# PCA9685Shield.net
KiCad netlist of a schematic drawn in EAGLE
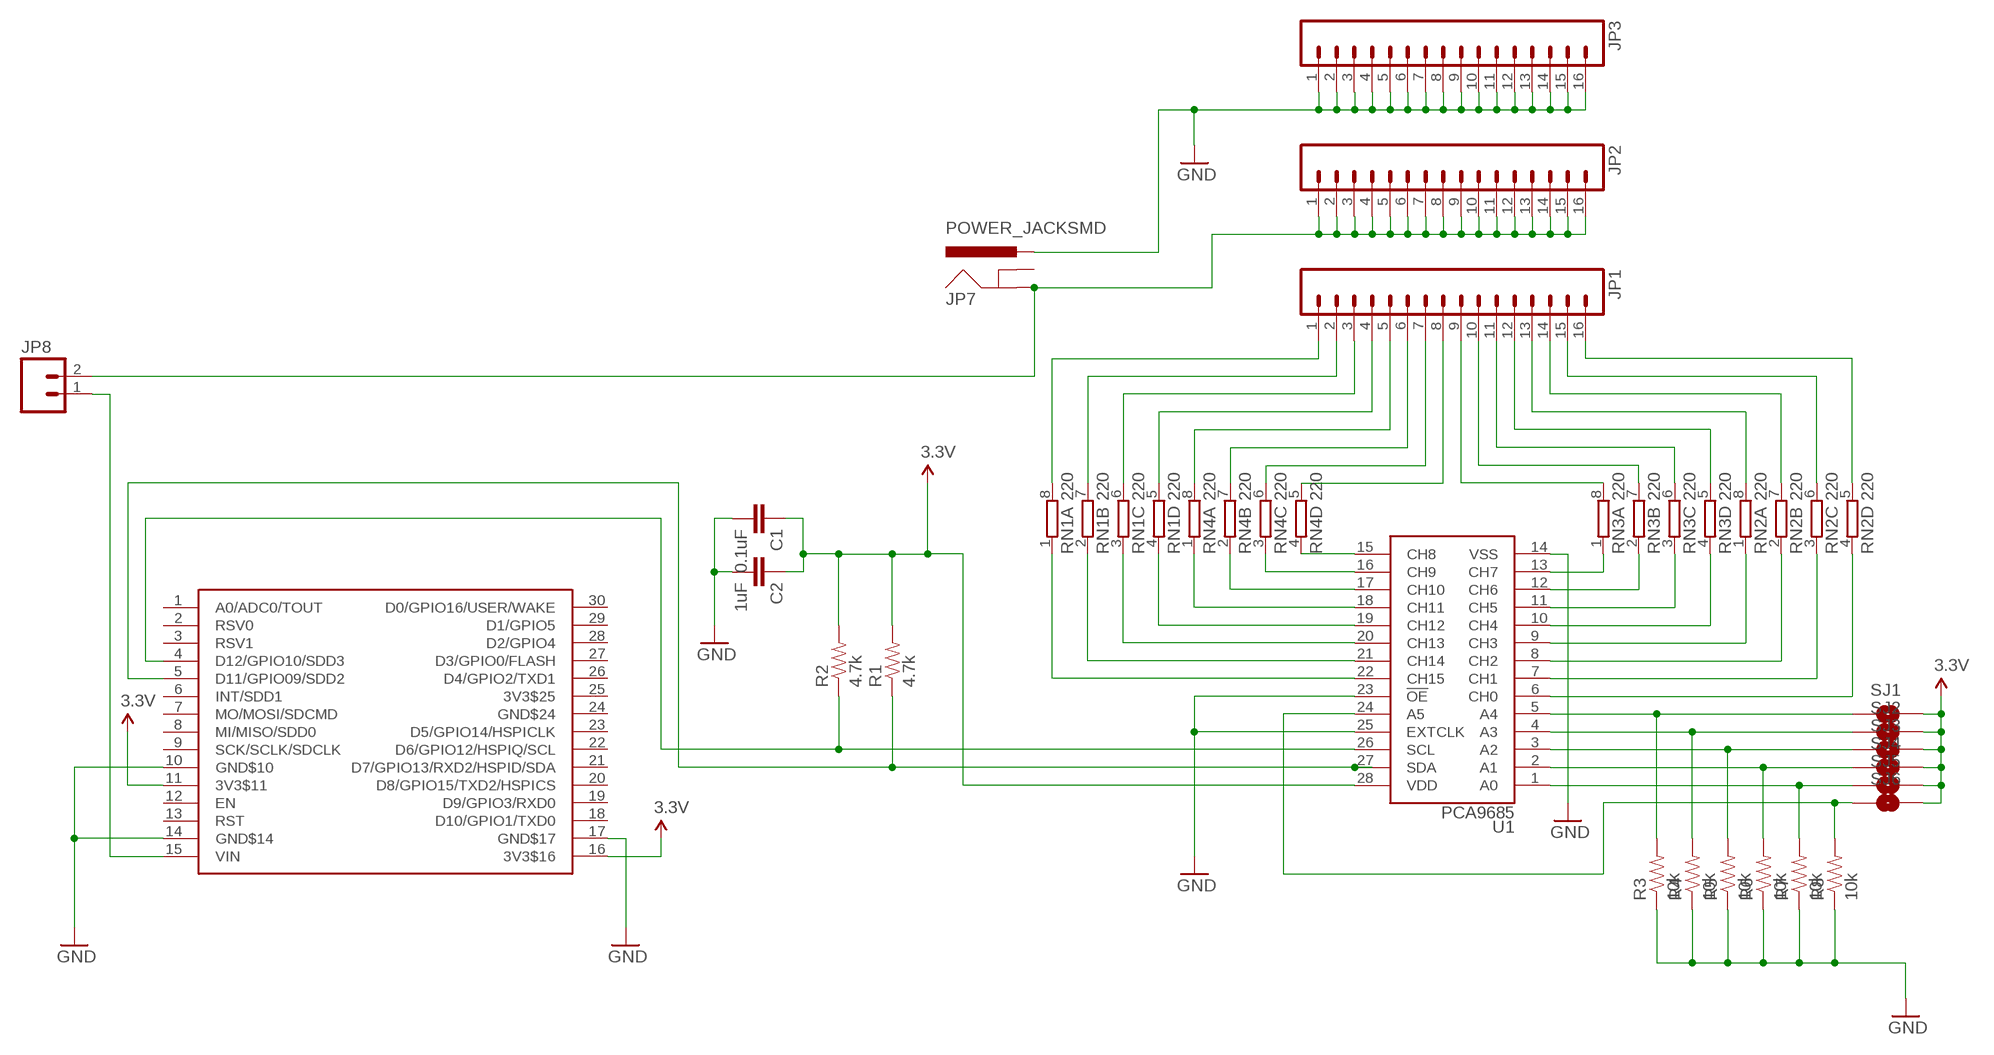
[diagram p0: schematic, sheet 1]

(export (version "E")
  (design (tool "Eeschema 10.0.6"))
  (components
    (comp (ref "C1")
      (value "0.1uF")
      (footprint "eagle-import:0402-CAP")
      (libsource (lib "eagle-import") (part "CAP0402-CAP"))
    )
    (comp (ref "C2")
      (value "1uF")
      (footprint "eagle-import:0402-CAP")
      (libsource (lib "eagle-import") (part "CAP0402-CAP"))
    )
    (comp (ref "JP1")
      (value "M161X16_NO_SILK")
      (footprint "eagle-import:1X16_NO_SILK")
      (libsource (lib "eagle-import") (part "M161X16_NO_SILK"))
    )
    (comp (ref "JP2")
      (value "M161X16_NO_SILK")
      (footprint "eagle-import:1X16_NO_SILK")
      (libsource (lib "eagle-import") (part "M161X16_NO_SILK"))
    )
    (comp (ref "JP3")
      (value "M161X16_NO_SILK")
      (footprint "eagle-import:1X16_NO_SILK")
      (libsource (lib "eagle-import") (part "M161X16_NO_SILK"))
    )
    (comp (ref "JP7")
      (value "POWER_JACKSMD")
      (footprint "eagle-import:POWER_JACK_SMD")
      (libsource (lib "eagle-import") (part "POWER_JACKSMD"))
    )
    (comp (ref "JP8")
      (value "M021X02_NO_SILK")
      (footprint "eagle-import:1X02_NO_SILK")
      (libsource (lib "eagle-import") (part "M021X02_NO_SILK"))
    )
    (comp (ref "R1")
      (value "4.7k")
      (footprint "eagle-import:0402-RES")
      (libsource (lib "eagle-import") (part "RESISTOR0402-RES"))
    )
    (comp (ref "R2")
      (value "4.7k")
      (footprint "eagle-import:0402-RES")
      (libsource (lib "eagle-import") (part "RESISTOR0402-RES"))
    )
    (comp (ref "R3")
      (value "10k")
      (footprint "eagle-import:0402-RES")
      (libsource (lib "eagle-import") (part "RESISTOR0402-RES"))
    )
    (comp (ref "R4")
      (value "10k")
      (footprint "eagle-import:0402-RES")
      (libsource (lib "eagle-import") (part "RESISTOR0402-RES"))
    )
    (comp (ref "R5")
      (value "10k")
      (footprint "eagle-import:0402-RES")
      (libsource (lib "eagle-import") (part "RESISTOR0402-RES"))
    )
    (comp (ref "R6")
      (value "10k")
      (footprint "eagle-import:0402-RES")
      (libsource (lib "eagle-import") (part "RESISTOR0402-RES"))
    )
    (comp (ref "R7")
      (value "10k")
      (footprint "eagle-import:0402-RES")
      (libsource (lib "eagle-import") (part "RESISTOR0402-RES"))
    )
    (comp (ref "R8")
      (value "10k")
      (footprint "eagle-import:0402-RES")
      (libsource (lib "eagle-import") (part "RESISTOR0402-RES"))
    )
    (comp (ref "RN1")
      (value "220")
      (footprint "eagle-import:EXBS8V")
      (libsource (lib "eagle-import") (part "4R-NEXBS8V"))
    )
    (comp (ref "RN2")
      (value "220")
      (footprint "eagle-import:EXBS8V")
      (libsource (lib "eagle-import") (part "4R-NEXBS8V"))
    )
    (comp (ref "RN3")
      (value "220")
      (footprint "eagle-import:EXBS8V")
      (libsource (lib "eagle-import") (part "4R-NEXBS8V"))
    )
    (comp (ref "RN4")
      (value "220")
      (footprint "eagle-import:EXBS8V")
      (libsource (lib "eagle-import") (part "4R-NEXBS8V"))
    )
    (comp (ref "SJ1")
      (value "SOLDERJUMPERNO")
      (footprint "eagle-import:SJ_2S-NO")
      (libsource (lib "eagle-import") (part "SOLDERJUMPERNO"))
    )
    (comp (ref "SJ2")
      (value "SOLDERJUMPERNO")
      (footprint "eagle-import:SJ_2S-NO")
      (libsource (lib "eagle-import") (part "SOLDERJUMPERNO"))
    )
    (comp (ref "SJ3")
      (value "SOLDERJUMPERNO")
      (footprint "eagle-import:SJ_2S-NO")
      (libsource (lib "eagle-import") (part "SOLDERJUMPERNO"))
    )
    (comp (ref "SJ4")
      (value "SOLDERJUMPERNO")
      (footprint "eagle-import:SJ_2S-NO")
      (libsource (lib "eagle-import") (part "SOLDERJUMPERNO"))
    )
    (comp (ref "SJ5")
      (value "SOLDERJUMPERNO")
      (footprint "eagle-import:SJ_2S-NO")
      (libsource (lib "eagle-import") (part "SOLDERJUMPERNO"))
    )
    (comp (ref "SJ6")
      (value "SOLDERJUMPERNO")
      (footprint "eagle-import:SJ_2S-NO")
      (libsource (lib "eagle-import") (part "SOLDERJUMPERNO"))
    )
    (comp (ref "U$1")
      (value "NERDSHIELD")
      (footprint "eagle-import:NERDUINO_STACK")
      (libsource (lib "eagle-import") (part "NERDSHIELD"))
    )
    (comp (ref "U1")
      (value "PCA9685")
      (footprint "eagle-import:TSSOP-28_4MM")
      (libsource (lib "eagle-import") (part "PCA9685"))
    )
  )
  (nets
    (net (code "1") (name "3.3V") (class "Default")
      (node (ref "C1") (pin "1") (pinfunction "1_1") (pintype "passive"))
      (node (ref "C2") (pin "1") (pinfunction "1_1") (pintype "passive"))
      (node (ref "R1") (pin "2") (pinfunction "2_2") (pintype "passive"))
      (node (ref "R2") (pin "2") (pinfunction "2_2") (pintype "passive"))
      (node (ref "SJ1") (pin "2") (pinfunction "2_2") (pintype "passive"))
      (node (ref "SJ2") (pin "2") (pinfunction "2_2") (pintype "passive"))
      (node (ref "SJ3") (pin "2") (pinfunction "2_2") (pintype "passive"))
      (node (ref "SJ4") (pin "2") (pinfunction "2_2") (pintype "passive"))
      (node (ref "SJ5") (pin "2") (pinfunction "2_2") (pintype "passive"))
      (node (ref "SJ6") (pin "2") (pinfunction "2_2") (pintype "passive"))
      (node (ref "U$1") (pin "11") (pinfunction "3V3$11_11") (pintype "bidirectional"))
      (node (ref "U$1") (pin "16") (pinfunction "3V3$16_16") (pintype "bidirectional"))
      (node (ref "U1") (pin "28") (pinfunction "VDD_28") (pintype "bidirectional"))
    )
    (net (code "2") (name "GND") (class "Default")
      (node (ref "C1") (pin "2") (pinfunction "2_2") (pintype "passive"))
      (node (ref "C2") (pin "2") (pinfunction "2_2") (pintype "passive"))
      (node (ref "JP3") (pin "1") (pinfunction "1_1") (pintype "passive"))
      (node (ref "JP3") (pin "10") (pinfunction "10_10") (pintype "passive"))
      (node (ref "JP3") (pin "11") (pinfunction "11_11") (pintype "passive"))
      (node (ref "JP3") (pin "12") (pinfunction "12_12") (pintype "passive"))
      (node (ref "JP3") (pin "13") (pinfunction "13_13") (pintype "passive"))
      (node (ref "JP3") (pin "14") (pinfunction "14_14") (pintype "passive"))
      (node (ref "JP3") (pin "15") (pinfunction "15_15") (pintype "passive"))
      (node (ref "JP3") (pin "16") (pinfunction "16_16") (pintype "passive"))
      (node (ref "JP3") (pin "2") (pinfunction "2_2") (pintype "passive"))
      (node (ref "JP3") (pin "3") (pinfunction "3_3") (pintype "passive"))
      (node (ref "JP3") (pin "4") (pinfunction "4_4") (pintype "passive"))
      (node (ref "JP3") (pin "5") (pinfunction "5_5") (pintype "passive"))
      (node (ref "JP3") (pin "6") (pinfunction "6_6") (pintype "passive"))
      (node (ref "JP3") (pin "7") (pinfunction "7_7") (pintype "passive"))
      (node (ref "JP3") (pin "8") (pinfunction "8_8") (pintype "passive"))
      (node (ref "JP3") (pin "9") (pinfunction "9_9") (pintype "passive"))
      (node (ref "JP7") (pin "VIN0") (pinfunction "PWR_VIN0") (pintype "bidirectional"))
      (node (ref "R3") (pin "1") (pinfunction "1_1") (pintype "passive"))
      (node (ref "R4") (pin "1") (pinfunction "1_1") (pintype "passive"))
      (node (ref "R5") (pin "1") (pinfunction "1_1") (pintype "passive"))
      (node (ref "R6") (pin "1") (pinfunction "1_1") (pintype "passive"))
      (node (ref "R7") (pin "1") (pinfunction "1_1") (pintype "passive"))
      (node (ref "R8") (pin "1") (pinfunction "1_1") (pintype "passive"))
      (node (ref "U$1") (pin "10") (pinfunction "GND$10_10") (pintype "bidirectional"))
      (node (ref "U$1") (pin "14") (pinfunction "GND$14_14") (pintype "bidirectional"))
      (node (ref "U$1") (pin "17") (pinfunction "GND$17_17") (pintype "bidirectional"))
      (node (ref "U1") (pin "14") (pinfunction "VSS_14") (pintype "bidirectional"))
      (node (ref "U1") (pin "23") (pinfunction "~{OE}_23") (pintype "bidirectional"))
      (node (ref "U1") (pin "25") (pinfunction "EXTCLK_25") (pintype "bidirectional"))
    )
    (net (code "3") (name "Net-(JP7-GND)") (class "Default")
      (node (ref "JP2") (pin "1") (pinfunction "1_1") (pintype "passive"))
      (node (ref "JP2") (pin "10") (pinfunction "10_10") (pintype "passive"))
      (node (ref "JP2") (pin "11") (pinfunction "11_11") (pintype "passive"))
      (node (ref "JP2") (pin "12") (pinfunction "12_12") (pintype "passive"))
      (node (ref "JP2") (pin "13") (pinfunction "13_13") (pintype "passive"))
      (node (ref "JP2") (pin "14") (pinfunction "14_14") (pintype "passive"))
      (node (ref "JP2") (pin "15") (pinfunction "15_15") (pintype "passive"))
      (node (ref "JP2") (pin "16") (pinfunction "16_16") (pintype "passive"))
      (node (ref "JP2") (pin "2") (pinfunction "2_2") (pintype "passive"))
      (node (ref "JP2") (pin "3") (pinfunction "3_3") (pintype "passive"))
      (node (ref "JP2") (pin "4") (pinfunction "4_4") (pintype "passive"))
      (node (ref "JP2") (pin "5") (pinfunction "5_5") (pintype "passive"))
      (node (ref "JP2") (pin "6") (pinfunction "6_6") (pintype "passive"))
      (node (ref "JP2") (pin "7") (pinfunction "7_7") (pintype "passive"))
      (node (ref "JP2") (pin "8") (pinfunction "8_8") (pintype "passive"))
      (node (ref "JP2") (pin "9") (pinfunction "9_9") (pintype "passive"))
      (node (ref "JP7") (pin "P$4") (pinfunction "GND_P$4") (pintype "bidirectional"))
      (node (ref "JP8") (pin "2") (pinfunction "2_2") (pintype "passive"))
    )
    (net (code "4") (name "Net-(RN1A-2)") (class "Default")
      (node (ref "JP1") (pin "1") (pinfunction "1_1") (pintype "passive"))
      (node (ref "RN1") (pin "8") (pinfunction "2_8") (pintype "passive"))
    )
    (net (code "5") (name "Net-(RN1B-1)") (class "Default")
      (node (ref "RN1") (pin "2") (pinfunction "1_2") (pintype "passive"))
      (node (ref "U1") (pin "21") (pinfunction "CH14_21") (pintype "bidirectional"))
    )
    (net (code "6") (name "Net-(RN1B-2)") (class "Default")
      (node (ref "JP1") (pin "2") (pinfunction "2_2") (pintype "passive"))
      (node (ref "RN1") (pin "7") (pinfunction "2_7") (pintype "passive"))
    )
    (net (code "7") (name "Net-(RN1C-1)") (class "Default")
      (node (ref "RN1") (pin "3") (pinfunction "1_3") (pintype "passive"))
      (node (ref "U1") (pin "20") (pinfunction "CH13_20") (pintype "bidirectional"))
    )
    (net (code "8") (name "Net-(RN1C-2)") (class "Default")
      (node (ref "JP1") (pin "3") (pinfunction "3_3") (pintype "passive"))
      (node (ref "RN1") (pin "6") (pinfunction "2_6") (pintype "passive"))
    )
    (net (code "9") (name "Net-(RN1D-1)") (class "Default")
      (node (ref "RN1") (pin "4") (pinfunction "1_4") (pintype "passive"))
      (node (ref "U1") (pin "19") (pinfunction "CH12_19") (pintype "bidirectional"))
    )
    (net (code "10") (name "Net-(RN1D-2)") (class "Default")
      (node (ref "JP1") (pin "4") (pinfunction "4_4") (pintype "passive"))
      (node (ref "RN1") (pin "5") (pinfunction "2_5") (pintype "passive"))
    )
    (net (code "11") (name "Net-(RN2A-2)") (class "Default")
      (node (ref "JP1") (pin "13") (pinfunction "13_13") (pintype "passive"))
      (node (ref "RN2") (pin "8") (pinfunction "2_8") (pintype "passive"))
    )
    (net (code "12") (name "Net-(RN2B-1)") (class "Default")
      (node (ref "RN2") (pin "2") (pinfunction "1_2") (pintype "passive"))
      (node (ref "U1") (pin "8") (pinfunction "CH2_8") (pintype "bidirectional"))
    )
    (net (code "13") (name "Net-(RN2B-2)") (class "Default")
      (node (ref "JP1") (pin "14") (pinfunction "14_14") (pintype "passive"))
      (node (ref "RN2") (pin "7") (pinfunction "2_7") (pintype "passive"))
    )
    (net (code "14") (name "Net-(RN2C-1)") (class "Default")
      (node (ref "RN2") (pin "3") (pinfunction "1_3") (pintype "passive"))
      (node (ref "U1") (pin "7") (pinfunction "CH1_7") (pintype "bidirectional"))
    )
    (net (code "15") (name "Net-(RN2C-2)") (class "Default")
      (node (ref "JP1") (pin "15") (pinfunction "15_15") (pintype "passive"))
      (node (ref "RN2") (pin "6") (pinfunction "2_6") (pintype "passive"))
    )
    (net (code "16") (name "Net-(RN2D-1)") (class "Default")
      (node (ref "RN2") (pin "4") (pinfunction "1_4") (pintype "passive"))
      (node (ref "U1") (pin "6") (pinfunction "CH0_6") (pintype "bidirectional"))
    )
    (net (code "17") (name "Net-(RN2D-2)") (class "Default")
      (node (ref "JP1") (pin "16") (pinfunction "16_16") (pintype "passive"))
      (node (ref "RN2") (pin "5") (pinfunction "2_5") (pintype "passive"))
    )
    (net (code "18") (name "Net-(RN3A-2)") (class "Default")
      (node (ref "JP1") (pin "9") (pinfunction "9_9") (pintype "passive"))
      (node (ref "RN3") (pin "8") (pinfunction "2_8") (pintype "passive"))
    )
    (net (code "19") (name "Net-(RN3B-1)") (class "Default")
      (node (ref "RN3") (pin "2") (pinfunction "1_2") (pintype "passive"))
      (node (ref "U1") (pin "12") (pinfunction "CH6_12") (pintype "bidirectional"))
    )
    (net (code "20") (name "Net-(RN3B-2)") (class "Default")
      (node (ref "JP1") (pin "10") (pinfunction "10_10") (pintype "passive"))
      (node (ref "RN3") (pin "7") (pinfunction "2_7") (pintype "passive"))
    )
    (net (code "21") (name "Net-(RN3C-1)") (class "Default")
      (node (ref "RN3") (pin "3") (pinfunction "1_3") (pintype "passive"))
      (node (ref "U1") (pin "11") (pinfunction "CH5_11") (pintype "bidirectional"))
    )
    (net (code "22") (name "Net-(RN3C-2)") (class "Default")
      (node (ref "JP1") (pin "11") (pinfunction "11_11") (pintype "passive"))
      (node (ref "RN3") (pin "6") (pinfunction "2_6") (pintype "passive"))
    )
    (net (code "23") (name "Net-(RN3D-1)") (class "Default")
      (node (ref "RN3") (pin "4") (pinfunction "1_4") (pintype "passive"))
      (node (ref "U1") (pin "10") (pinfunction "CH4_10") (pintype "bidirectional"))
    )
    (net (code "24") (name "Net-(RN3D-2)") (class "Default")
      (node (ref "JP1") (pin "12") (pinfunction "12_12") (pintype "passive"))
      (node (ref "RN3") (pin "5") (pinfunction "2_5") (pintype "passive"))
    )
    (net (code "25") (name "Net-(RN4A-2)") (class "Default")
      (node (ref "JP1") (pin "5") (pinfunction "5_5") (pintype "passive"))
      (node (ref "RN4") (pin "8") (pinfunction "2_8") (pintype "passive"))
    )
    (net (code "26") (name "Net-(RN4B-1)") (class "Default")
      (node (ref "RN4") (pin "2") (pinfunction "1_2") (pintype "passive"))
      (node (ref "U1") (pin "17") (pinfunction "CH10_17") (pintype "bidirectional"))
    )
    (net (code "27") (name "Net-(RN4B-2)") (class "Default")
      (node (ref "JP1") (pin "6") (pinfunction "6_6") (pintype "passive"))
      (node (ref "RN4") (pin "7") (pinfunction "2_7") (pintype "passive"))
    )
    (net (code "28") (name "Net-(RN4C-1)") (class "Default")
      (node (ref "RN4") (pin "3") (pinfunction "1_3") (pintype "passive"))
      (node (ref "U1") (pin "16") (pinfunction "CH9_16") (pintype "bidirectional"))
    )
    (net (code "29") (name "Net-(RN4C-2)") (class "Default")
      (node (ref "JP1") (pin "7") (pinfunction "7_7") (pintype "passive"))
      (node (ref "RN4") (pin "6") (pinfunction "2_6") (pintype "passive"))
    )
    (net (code "30") (name "Net-(RN4D-1)") (class "Default")
      (node (ref "RN4") (pin "4") (pinfunction "1_4") (pintype "passive"))
      (node (ref "U1") (pin "15") (pinfunction "CH8_15") (pintype "bidirectional"))
    )
    (net (code "31") (name "Net-(RN4D-2)") (class "Default")
      (node (ref "JP1") (pin "8") (pinfunction "8_8") (pintype "passive"))
      (node (ref "RN4") (pin "5") (pinfunction "2_5") (pintype "passive"))
    )
    (net (code "32") (name "Net-(U$1-D11{slash}GPIO09{slash}SDD2)") (class "Default")
      (node (ref "R1") (pin "1") (pinfunction "1_1") (pintype "passive"))
      (node (ref "U$1") (pin "5") (pinfunction "D11/GPIO09/SDD2_5") (pintype "bidirectional"))
      (node (ref "U1") (pin "27") (pinfunction "SDA_27") (pintype "bidirectional"))
    )
    (net (code "33") (name "Net-(U$1-D12{slash}GPIO10{slash}SDD3)") (class "Default")
      (node (ref "R2") (pin "1") (pinfunction "1_1") (pintype "passive"))
      (node (ref "U$1") (pin "4") (pinfunction "D12/GPIO10/SDD3_4") (pintype "bidirectional"))
      (node (ref "U1") (pin "26") (pinfunction "SCL_26") (pintype "bidirectional"))
    )
    (net (code "34") (name "Net-(U$1-VIN)") (class "Default")
      (node (ref "JP8") (pin "1") (pinfunction "1_1") (pintype "passive"))
      (node (ref "U$1") (pin "15") (pinfunction "VIN_15") (pintype "bidirectional"))
    )
    (net (code "35") (name "Net-(U1-A0)") (class "Default")
      (node (ref "R7") (pin "2") (pinfunction "2_2") (pintype "passive"))
      (node (ref "SJ5") (pin "1") (pinfunction "1_1") (pintype "passive"))
      (node (ref "U1") (pin "1") (pinfunction "A0_1") (pintype "bidirectional"))
    )
    (net (code "36") (name "Net-(U1-A1)") (class "Default")
      (node (ref "R6") (pin "2") (pinfunction "2_2") (pintype "passive"))
      (node (ref "SJ4") (pin "1") (pinfunction "1_1") (pintype "passive"))
      (node (ref "U1") (pin "2") (pinfunction "A1_2") (pintype "bidirectional"))
    )
    (net (code "37") (name "Net-(U1-A2)") (class "Default")
      (node (ref "R5") (pin "2") (pinfunction "2_2") (pintype "passive"))
      (node (ref "SJ3") (pin "1") (pinfunction "1_1") (pintype "passive"))
      (node (ref "U1") (pin "3") (pinfunction "A2_3") (pintype "bidirectional"))
    )
    (net (code "38") (name "Net-(U1-A3)") (class "Default")
      (node (ref "R4") (pin "2") (pinfunction "2_2") (pintype "passive"))
      (node (ref "SJ2") (pin "1") (pinfunction "1_1") (pintype "passive"))
      (node (ref "U1") (pin "4") (pinfunction "A3_4") (pintype "bidirectional"))
    )
    (net (code "39") (name "Net-(U1-A4)") (class "Default")
      (node (ref "R3") (pin "2") (pinfunction "2_2") (pintype "passive"))
      (node (ref "SJ1") (pin "1") (pinfunction "1_1") (pintype "passive"))
      (node (ref "U1") (pin "5") (pinfunction "A4_5") (pintype "bidirectional"))
    )
    (net (code "40") (name "Net-(U1-A5)") (class "Default")
      (node (ref "R8") (pin "2") (pinfunction "2_2") (pintype "passive"))
      (node (ref "SJ6") (pin "1") (pinfunction "1_1") (pintype "passive"))
      (node (ref "U1") (pin "24") (pinfunction "A5_24") (pintype "bidirectional"))
    )
    (net (code "41") (name "Net-(U1-CH3)") (class "Default")
      (node (ref "RN2") (pin "1") (pinfunction "1_1") (pintype "passive"))
      (node (ref "U1") (pin "9") (pinfunction "CH3_9") (pintype "bidirectional"))
    )
    (net (code "42") (name "Net-(U1-CH7)") (class "Default")
      (node (ref "RN3") (pin "1") (pinfunction "1_1") (pintype "passive"))
      (node (ref "U1") (pin "13") (pinfunction "CH7_13") (pintype "bidirectional"))
    )
    (net (code "43") (name "Net-(U1-CH11)") (class "Default")
      (node (ref "RN4") (pin "1") (pinfunction "1_1") (pintype "passive"))
      (node (ref "U1") (pin "18") (pinfunction "CH11_18") (pintype "bidirectional"))
    )
    (net (code "44") (name "Net-(U1-CH15)") (class "Default")
      (node (ref "RN1") (pin "1") (pinfunction "1_1") (pintype "passive"))
      (node (ref "U1") (pin "22") (pinfunction "CH15_22") (pintype "bidirectional"))
    )
    (net (code "45") (name "unconnected-(JP7-GNDBREAK-PadGND)") (class "Default")
      (node (ref "JP7") (pin "GND") (pinfunction "GNDBREAK_GND") (pintype "bidirectional"))
    )
    (net (code "46") (name "unconnected-(U$1-3V3$25-Pad25)") (class "Default")
      (node (ref "U$1") (pin "25") (pinfunction "3V3$25_25") (pintype "bidirectional"))
    )
    (net (code "47") (name "unconnected-(U$1-A0{slash}ADC0{slash}TOUT-Pad1)") (class "Default")
      (node (ref "U$1") (pin "1") (pinfunction "A0/ADC0/TOUT_1") (pintype "bidirectional"))
    )
    (net (code "48") (name "unconnected-(U$1-D0{slash}GPIO16{slash}USER{slash}WAKE-Pad30)") (class "Default")
      (node (ref "U$1") (pin "30") (pinfunction "D0/GPIO16/USER/WAKE_30") (pintype "bidirectional"))
    )
    (net (code "49") (name "unconnected-(U$1-D1{slash}GPIO5-Pad29)") (class "Default")
      (node (ref "U$1") (pin "29") (pinfunction "D1/GPIO5_29") (pintype "bidirectional"))
    )
    (net (code "50") (name "unconnected-(U$1-D2{slash}GPIO4-Pad28)") (class "Default")
      (node (ref "U$1") (pin "28") (pinfunction "D2/GPIO4_28") (pintype "bidirectional"))
    )
    (net (code "51") (name "unconnected-(U$1-D3{slash}GPIO0{slash}FLASH-Pad27)") (class "Default")
      (node (ref "U$1") (pin "27") (pinfunction "D3/GPIO0/FLASH_27") (pintype "bidirectional"))
    )
    (net (code "52") (name "unconnected-(U$1-D4{slash}GPIO2{slash}TXD1-Pad26)") (class "Default")
      (node (ref "U$1") (pin "26") (pinfunction "D4/GPIO2/TXD1_26") (pintype "bidirectional"))
    )
    (net (code "53") (name "unconnected-(U$1-D5{slash}GPIO14{slash}HSPICLK-Pad23)") (class "Default")
      (node (ref "U$1") (pin "23") (pinfunction "D5/GPIO14/HSPICLK_23") (pintype "bidirectional"))
    )
    (net (code "54") (name "unconnected-(U$1-D6{slash}GPIO12{slash}HSPIQ{slash}SCL-Pad22)") (class "Default")
      (node (ref "U$1") (pin "22") (pinfunction "D6/GPIO12/HSPIQ/SCL_22") (pintype "bidirectional"))
    )
    (net (code "55") (name "unconnected-(U$1-D7{slash}GPIO13{slash}RXD2{slash}HSPID{slash}SDA-Pad21)") (class "Default")
      (node (ref "U$1") (pin "21") (pinfunction "D7/GPIO13/RXD2/HSPID/SDA_21") (pintype "bidirectional"))
    )
    (net (code "56") (name "unconnected-(U$1-D8{slash}GPIO15{slash}TXD2{slash}HSPICS-Pad20)") (class "Default")
      (node (ref "U$1") (pin "20") (pinfunction "D8/GPIO15/TXD2/HSPICS_20") (pintype "bidirectional"))
    )
    (net (code "57") (name "unconnected-(U$1-D9{slash}GPIO3{slash}RXD0-Pad19)") (class "Default")
      (node (ref "U$1") (pin "19") (pinfunction "D9/GPIO3/RXD0_19") (pintype "bidirectional"))
    )
    (net (code "58") (name "unconnected-(U$1-D10{slash}GPIO1{slash}TXD0-Pad18)") (class "Default")
      (node (ref "U$1") (pin "18") (pinfunction "D10/GPIO1/TXD0_18") (pintype "bidirectional"))
    )
    (net (code "59") (name "unconnected-(U$1-EN-Pad12)") (class "Default")
      (node (ref "U$1") (pin "12") (pinfunction "EN_12") (pintype "bidirectional"))
    )
    (net (code "60") (name "unconnected-(U$1-GND$24-Pad24)") (class "Default")
      (node (ref "U$1") (pin "24") (pinfunction "GND$24_24") (pintype "bidirectional"))
    )
    (net (code "61") (name "unconnected-(U$1-INT{slash}SDD1-Pad6)") (class "Default")
      (node (ref "U$1") (pin "6") (pinfunction "INT/SDD1_6") (pintype "bidirectional"))
    )
    (net (code "62") (name "unconnected-(U$1-MI{slash}MISO{slash}SDD0-Pad8)") (class "Default")
      (node (ref "U$1") (pin "8") (pinfunction "MI/MISO/SDD0_8") (pintype "bidirectional"))
    )
    (net (code "63") (name "unconnected-(U$1-MO{slash}MOSI{slash}SDCMD-Pad7)") (class "Default")
      (node (ref "U$1") (pin "7") (pinfunction "MO/MOSI/SDCMD_7") (pintype "bidirectional"))
    )
    (net (code "64") (name "unconnected-(U$1-RST-Pad13)") (class "Default")
      (node (ref "U$1") (pin "13") (pinfunction "RST_13") (pintype "bidirectional"))
    )
    (net (code "65") (name "unconnected-(U$1-RSV0-Pad2)") (class "Default")
      (node (ref "U$1") (pin "2") (pinfunction "RSV0_2") (pintype "bidirectional"))
    )
    (net (code "66") (name "unconnected-(U$1-RSV1-Pad3)") (class "Default")
      (node (ref "U$1") (pin "3") (pinfunction "RSV1_3") (pintype "bidirectional"))
    )
    (net (code "67") (name "unconnected-(U$1-SCK{slash}SCLK{slash}SDCLK-Pad9)") (class "Default")
      (node (ref "U$1") (pin "9") (pinfunction "SCK/SCLK/SDCLK_9") (pintype "bidirectional"))
    )
  )
)
